# LB_BIT_3IN_3OUT-LARGE-v03_1_1x.net
KiCad netlist of a schematic drawn in EAGLE
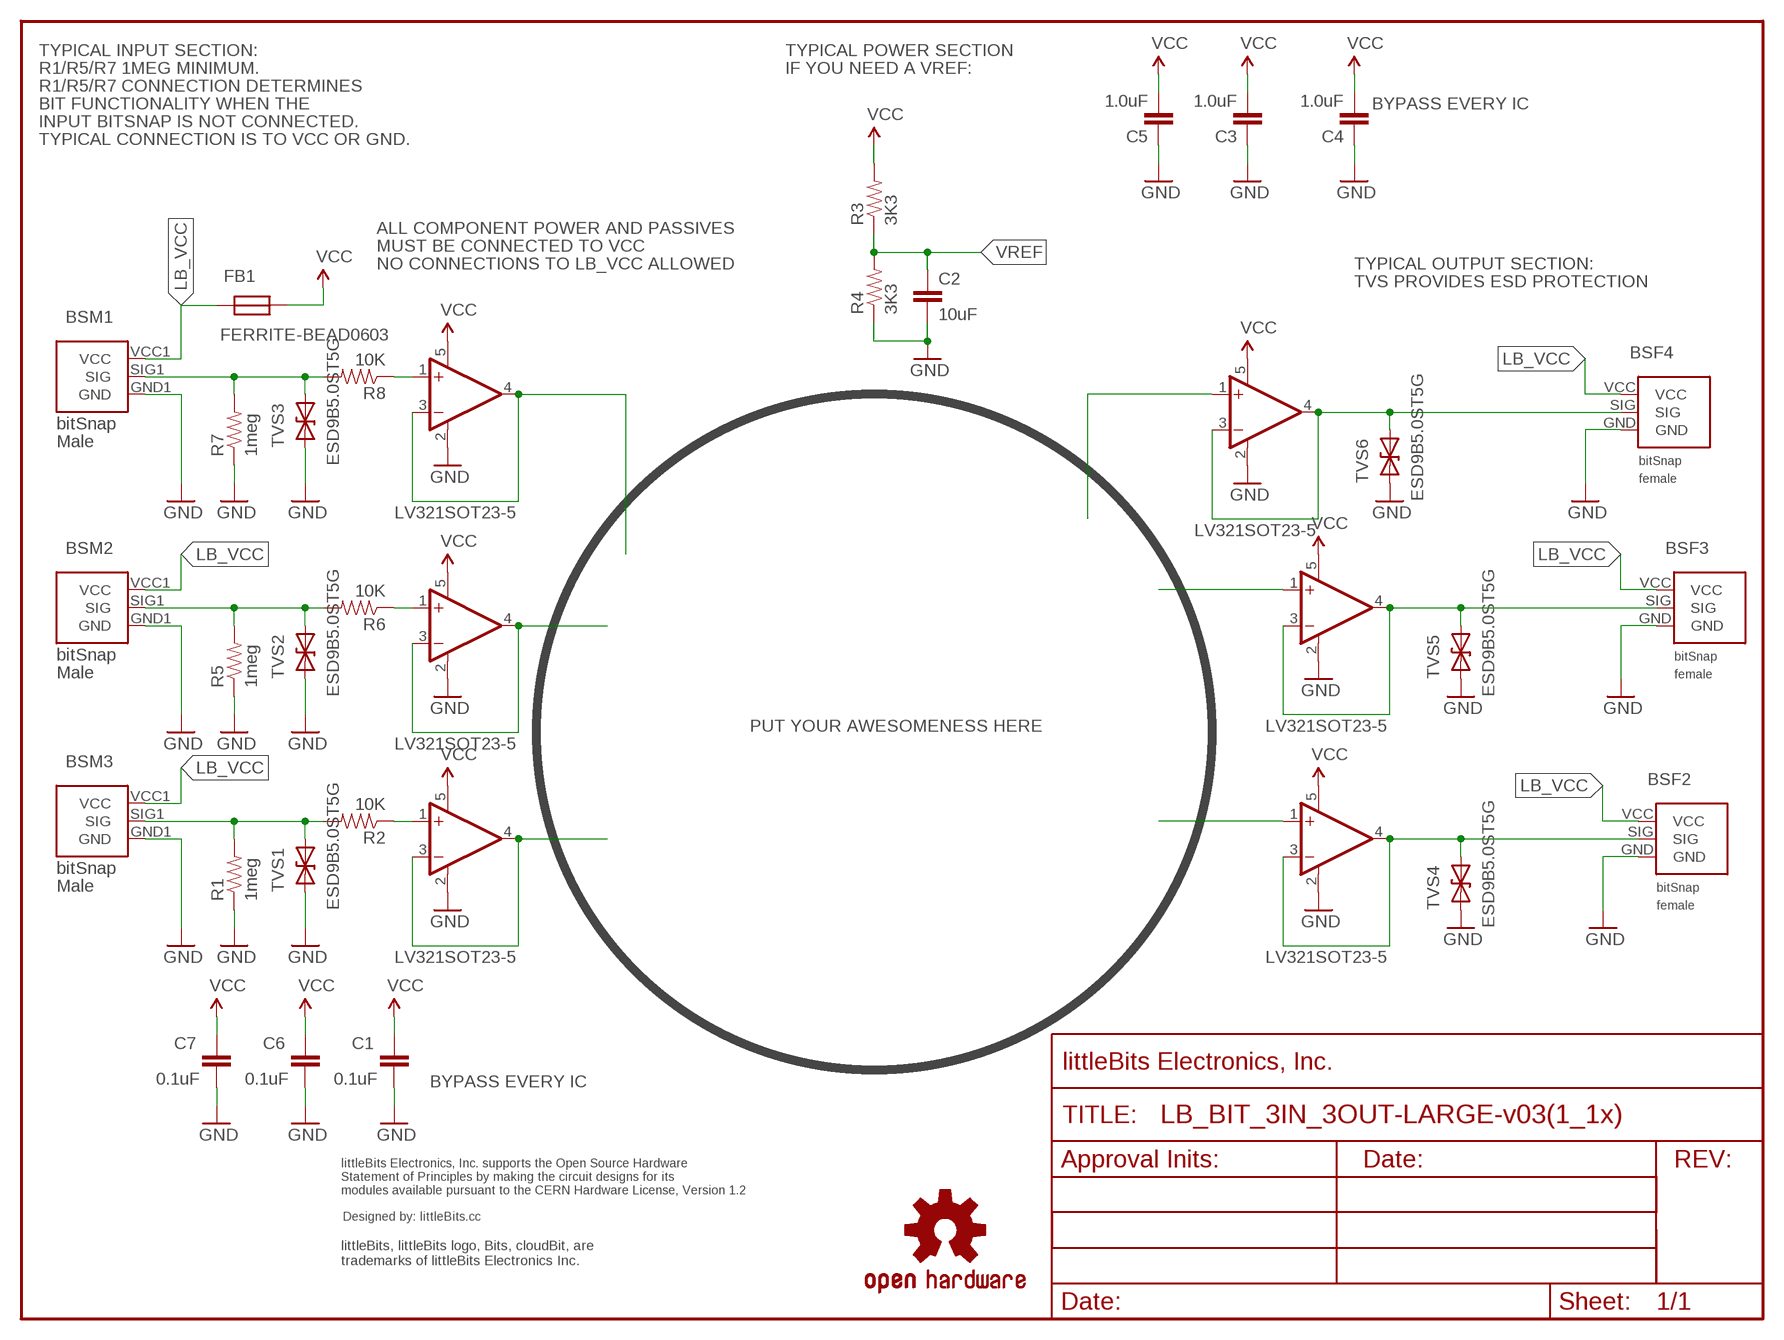
[diagram p0: schematic, sheet 1]

(export (version "E")
  (design (tool "Eeschema 10.0.6"))
  (components
    (comp (ref "BSF2")
      (value "BITSNAP_V03_FEMALE")
      (footprint "eagle-import:BITSNAP_V03_FEMALE")
      (libsource (lib "eagle-import") (part "BITSNAP_V03_FEMALE"))
    )
    (comp (ref "BSF3")
      (value "BITSNAP_V03_FEMALE")
      (footprint "eagle-import:BITSNAP_V03_FEMALE")
      (libsource (lib "eagle-import") (part "BITSNAP_V03_FEMALE"))
    )
    (comp (ref "BSF4")
      (value "BITSNAP_V03_FEMALE")
      (footprint "eagle-import:BITSNAP_V03_FEMALE")
      (libsource (lib "eagle-import") (part "BITSNAP_V03_FEMALE"))
    )
    (comp (ref "BSM1")
      (value "BITSNAP_V03_MALE")
      (footprint "eagle-import:BITSNAP_V03_MALE")
      (libsource (lib "eagle-import") (part "BITSNAP_V03_MALE"))
    )
    (comp (ref "BSM2")
      (value "BITSNAP_V03_MALE")
      (footprint "eagle-import:BITSNAP_V03_MALE")
      (libsource (lib "eagle-import") (part "BITSNAP_V03_MALE"))
    )
    (comp (ref "BSM3")
      (value "BITSNAP_V03_MALE")
      (footprint "eagle-import:BITSNAP_V03_MALE")
      (libsource (lib "eagle-import") (part "BITSNAP_V03_MALE"))
    )
    (comp (ref "C1")
      (value "0.1uF")
      (footprint "eagle-import:CAP-0603")
      (libsource (lib "eagle-import") (part "CAPCAP-0603"))
    )
    (comp (ref "C2")
      (value "10uF")
      (footprint "eagle-import:CAP-0603")
      (libsource (lib "eagle-import") (part "CAPCAP-0603"))
    )
    (comp (ref "C3")
      (value "1.0uF")
      (footprint "eagle-import:CAP-0603")
      (libsource (lib "eagle-import") (part "CAPCAP-0603"))
    )
    (comp (ref "C4")
      (value "1.0uF")
      (footprint "eagle-import:CAP-0603")
      (libsource (lib "eagle-import") (part "CAPCAP-0603"))
    )
    (comp (ref "C5")
      (value "1.0uF")
      (footprint "eagle-import:CAP-0603")
      (libsource (lib "eagle-import") (part "CAPCAP-0603"))
    )
    (comp (ref "C6")
      (value "0.1uF")
      (footprint "eagle-import:CAP-0603")
      (libsource (lib "eagle-import") (part "CAPCAP-0603"))
    )
    (comp (ref "C7")
      (value "0.1uF")
      (footprint "eagle-import:CAP-0603")
      (libsource (lib "eagle-import") (part "CAPCAP-0603"))
    )
    (comp (ref "FB1")
      (value "FERRITE-BEAD0603")
      (footprint "eagle-import:R0603")
      (libsource (lib "eagle-import") (part "FERRITE-BEAD0603"))
    )
    (comp (ref "FRAME1")
      (value "FRAME-LETTER")
      (footprint "eagle-import:FABDWG01-OHW")
      (libsource (lib "eagle-import") (part "FRAME-LETTER"))
    )
    (comp (ref "R1")
      (value "1meg")
      (footprint "eagle-import:RES-0603")
      (libsource (lib "eagle-import") (part "RESISTOR0603"))
    )
    (comp (ref "R2")
      (value "10K")
      (footprint "eagle-import:RES-0603")
      (libsource (lib "eagle-import") (part "RESISTOR0603"))
    )
    (comp (ref "R3")
      (value "3K3")
      (footprint "eagle-import:RES-0603")
      (libsource (lib "eagle-import") (part "RESISTOR0603"))
    )
    (comp (ref "R4")
      (value "3K3")
      (footprint "eagle-import:RES-0603")
      (libsource (lib "eagle-import") (part "RESISTOR0603"))
    )
    (comp (ref "R5")
      (value "1meg")
      (footprint "eagle-import:RES-0603")
      (libsource (lib "eagle-import") (part "RESISTOR0603"))
    )
    (comp (ref "R6")
      (value "10K")
      (footprint "eagle-import:RES-0603")
      (libsource (lib "eagle-import") (part "RESISTOR0603"))
    )
    (comp (ref "R7")
      (value "1meg")
      (footprint "eagle-import:RES-0603")
      (libsource (lib "eagle-import") (part "RESISTOR0603"))
    )
    (comp (ref "R8")
      (value "10K")
      (footprint "eagle-import:RES-0603")
      (libsource (lib "eagle-import") (part "RESISTOR0603"))
    )
    (comp (ref "TVS1")
      (value "ESD9B5.0ST5G")
      (footprint "eagle-import:SOD-923")
      (libsource (lib "eagle-import") (part "DIODE-TVSSOD-923"))
    )
    (comp (ref "TVS2")
      (value "ESD9B5.0ST5G")
      (footprint "eagle-import:SOD-923")
      (libsource (lib "eagle-import") (part "DIODE-TVSSOD-923"))
    )
    (comp (ref "TVS3")
      (value "ESD9B5.0ST5G")
      (footprint "eagle-import:SOD-923")
      (libsource (lib "eagle-import") (part "DIODE-TVSSOD-923"))
    )
    (comp (ref "TVS4")
      (value "ESD9B5.0ST5G")
      (footprint "eagle-import:SOD-923")
      (libsource (lib "eagle-import") (part "DIODE-TVSSOD-923"))
    )
    (comp (ref "TVS5")
      (value "ESD9B5.0ST5G")
      (footprint "eagle-import:SOD-923")
      (libsource (lib "eagle-import") (part "DIODE-TVSSOD-923"))
    )
    (comp (ref "TVS6")
      (value "ESD9B5.0ST5G")
      (footprint "eagle-import:SOD-923")
      (libsource (lib "eagle-import") (part "DIODE-TVSSOD-923"))
    )
    (comp (ref "U$1")
      (value "OSHWCREDIT")
      (footprint "eagle-import:OSHWCREDIT")
      (libsource (lib "eagle-import") (part "OSHWCREDIT"))
    )
    (comp (ref "U$70")
      (value "OSHW-LOGOL")
      (footprint "eagle-import:OSHW-LOGO-L")
      (libsource (lib "eagle-import") (part "OSHW-LOGOL"))
    )
    (comp (ref "U1")
      (value "LV321SOT23-5")
      (footprint "eagle-import:SOT23-5")
      (libsource (lib "eagle-import") (part "LV321SOT23-5"))
    )
    (comp (ref "U2")
      (value "LV321SOT23-5")
      (footprint "eagle-import:SOT23-5")
      (libsource (lib "eagle-import") (part "LV321SOT23-5"))
    )
    (comp (ref "U3")
      (value "LV321SOT23-5")
      (footprint "eagle-import:SOT23-5")
      (libsource (lib "eagle-import") (part "LV321SOT23-5"))
    )
    (comp (ref "U4")
      (value "LV321SOT23-5")
      (footprint "eagle-import:SOT23-5")
      (libsource (lib "eagle-import") (part "LV321SOT23-5"))
    )
    (comp (ref "U5")
      (value "LV321SOT23-5")
      (footprint "eagle-import:SOT23-5")
      (libsource (lib "eagle-import") (part "LV321SOT23-5"))
    )
    (comp (ref "U6")
      (value "LV321SOT23-5")
      (footprint "eagle-import:SOT23-5")
      (libsource (lib "eagle-import") (part "LV321SOT23-5"))
    )
  )
  (nets
    (net (code "1") (name "GND") (class "Default")
      (node (ref "BSF2") (pin "GND") (pinfunction "GND_GND") (pintype "bidirectional"))
      (node (ref "BSF3") (pin "GND") (pinfunction "GND_GND") (pintype "bidirectional"))
      (node (ref "BSF4") (pin "GND") (pinfunction "GND_GND") (pintype "bidirectional"))
      (node (ref "BSM1") (pin "GND1") (pinfunction "GND_GND1") (pintype "bidirectional"))
      (node (ref "BSM2") (pin "GND1") (pinfunction "GND_GND1") (pintype "bidirectional"))
      (node (ref "BSM3") (pin "GND1") (pinfunction "GND_GND1") (pintype "bidirectional"))
      (node (ref "C1") (pin "2") (pinfunction "2_2") (pintype "passive"))
      (node (ref "C2") (pin "2") (pinfunction "2_2") (pintype "passive"))
      (node (ref "C3") (pin "1") (pinfunction "1_1") (pintype "passive"))
      (node (ref "C4") (pin "1") (pinfunction "1_1") (pintype "passive"))
      (node (ref "C5") (pin "1") (pinfunction "1_1") (pintype "passive"))
      (node (ref "C6") (pin "2") (pinfunction "2_2") (pintype "passive"))
      (node (ref "C7") (pin "2") (pinfunction "2_2") (pintype "passive"))
      (node (ref "R1") (pin "1") (pinfunction "1_1") (pintype "passive"))
      (node (ref "R4") (pin "1") (pinfunction "1_1") (pintype "passive"))
      (node (ref "R5") (pin "1") (pinfunction "1_1") (pintype "passive"))
      (node (ref "R7") (pin "1") (pinfunction "1_1") (pintype "passive"))
      (node (ref "TVS1") (pin "1") (pinfunction "A_1") (pintype "passive"))
      (node (ref "TVS2") (pin "1") (pinfunction "A_1") (pintype "passive"))
      (node (ref "TVS3") (pin "1") (pinfunction "A_1") (pintype "passive"))
      (node (ref "TVS4") (pin "1") (pinfunction "A_1") (pintype "passive"))
      (node (ref "TVS5") (pin "1") (pinfunction "A_1") (pintype "passive"))
      (node (ref "TVS6") (pin "1") (pinfunction "A_1") (pintype "passive"))
      (node (ref "U1") (pin "2") (pinfunction "V-_2") (pintype "power_in"))
      (node (ref "U2") (pin "2") (pinfunction "V-_2") (pintype "power_in"))
      (node (ref "U3") (pin "2") (pinfunction "V-_2") (pintype "power_in"))
      (node (ref "U4") (pin "2") (pinfunction "V-_2") (pintype "power_in"))
      (node (ref "U5") (pin "2") (pinfunction "V-_2") (pintype "power_in"))
      (node (ref "U6") (pin "2") (pinfunction "V-_2") (pintype "power_in"))
    )
    (net (code "2") (name "LB_VCC") (class "Default")
      (node (ref "BSF2") (pin "VCC") (pinfunction "VCC_VCC") (pintype "bidirectional"))
      (node (ref "BSF3") (pin "VCC") (pinfunction "VCC_VCC") (pintype "bidirectional"))
      (node (ref "BSF4") (pin "VCC") (pinfunction "VCC_VCC") (pintype "bidirectional"))
      (node (ref "BSM1") (pin "VCC1") (pinfunction "VCC_VCC1") (pintype "bidirectional"))
      (node (ref "BSM2") (pin "VCC1") (pinfunction "VCC_VCC1") (pintype "bidirectional"))
      (node (ref "BSM3") (pin "VCC1") (pinfunction "VCC_VCC1") (pintype "bidirectional"))
      (node (ref "FB1") (pin "2") (pinfunction "P$2_2") (pintype "bidirectional"))
    )
    (net (code "3") (name "Net-(BSM1-SIG)") (class "Default")
      (node (ref "BSM1") (pin "SIG1") (pinfunction "SIG_SIG1") (pintype "bidirectional"))
      (node (ref "R7") (pin "2") (pinfunction "2_2") (pintype "passive"))
      (node (ref "R8") (pin "2") (pinfunction "2_2") (pintype "passive"))
      (node (ref "TVS3") (pin "2") (pinfunction "C_2") (pintype "passive"))
    )
    (net (code "4") (name "Net-(BSM2-SIG)") (class "Default")
      (node (ref "BSM2") (pin "SIG1") (pinfunction "SIG_SIG1") (pintype "bidirectional"))
      (node (ref "R5") (pin "2") (pinfunction "2_2") (pintype "passive"))
      (node (ref "R6") (pin "2") (pinfunction "2_2") (pintype "passive"))
      (node (ref "TVS2") (pin "2") (pinfunction "C_2") (pintype "passive"))
    )
    (net (code "5") (name "Net-(BSM3-SIG)") (class "Default")
      (node (ref "BSM3") (pin "SIG1") (pinfunction "SIG_SIG1") (pintype "bidirectional"))
      (node (ref "R1") (pin "2") (pinfunction "2_2") (pintype "passive"))
      (node (ref "R2") (pin "2") (pinfunction "2_2") (pintype "passive"))
      (node (ref "TVS1") (pin "2") (pinfunction "C_2") (pintype "passive"))
    )
    (net (code "6") (name "Net-(TVS4-C)") (class "Default")
      (node (ref "BSF2") (pin "SIG") (pinfunction "SIG_SIG") (pintype "bidirectional"))
      (node (ref "TVS4") (pin "2") (pinfunction "C_2") (pintype "passive"))
      (node (ref "U4") (pin "3") (pinfunction "-IN_3") (pintype "input"))
      (node (ref "U4") (pin "4") (pinfunction "OUT_4") (pintype "output"))
    )
    (net (code "7") (name "Net-(TVS5-C)") (class "Default")
      (node (ref "BSF3") (pin "SIG") (pinfunction "SIG_SIG") (pintype "bidirectional"))
      (node (ref "TVS5") (pin "2") (pinfunction "C_2") (pintype "passive"))
      (node (ref "U5") (pin "3") (pinfunction "-IN_3") (pintype "input"))
      (node (ref "U5") (pin "4") (pinfunction "OUT_4") (pintype "output"))
    )
    (net (code "8") (name "Net-(TVS6-C)") (class "Default")
      (node (ref "BSF4") (pin "SIG") (pinfunction "SIG_SIG") (pintype "bidirectional"))
      (node (ref "TVS6") (pin "2") (pinfunction "C_2") (pintype "passive"))
      (node (ref "U6") (pin "3") (pinfunction "-IN_3") (pintype "input"))
      (node (ref "U6") (pin "4") (pinfunction "OUT_4") (pintype "output"))
    )
    (net (code "9") (name "Net-(U1-+IN)") (class "Default")
      (node (ref "R2") (pin "1") (pinfunction "1_1") (pintype "passive"))
      (node (ref "U1") (pin "1") (pinfunction "+IN_1") (pintype "input"))
    )
    (net (code "10") (name "Net-(U1--IN)") (class "Default")
      (node (ref "U1") (pin "3") (pinfunction "-IN_3") (pintype "input"))
      (node (ref "U1") (pin "4") (pinfunction "OUT_4") (pintype "output"))
    )
    (net (code "11") (name "Net-(U2-+IN)") (class "Default")
      (node (ref "R6") (pin "1") (pinfunction "1_1") (pintype "passive"))
      (node (ref "U2") (pin "1") (pinfunction "+IN_1") (pintype "input"))
    )
    (net (code "12") (name "Net-(U2--IN)") (class "Default")
      (node (ref "U2") (pin "3") (pinfunction "-IN_3") (pintype "input"))
      (node (ref "U2") (pin "4") (pinfunction "OUT_4") (pintype "output"))
    )
    (net (code "13") (name "Net-(U3-+IN)") (class "Default")
      (node (ref "R8") (pin "1") (pinfunction "1_1") (pintype "passive"))
      (node (ref "U3") (pin "1") (pinfunction "+IN_1") (pintype "input"))
    )
    (net (code "14") (name "Net-(U3--IN)") (class "Default")
      (node (ref "U3") (pin "3") (pinfunction "-IN_3") (pintype "input"))
      (node (ref "U3") (pin "4") (pinfunction "OUT_4") (pintype "output"))
    )
    (net (code "15") (name "VCC") (class "Default")
      (node (ref "C1") (pin "1") (pinfunction "1_1") (pintype "passive"))
      (node (ref "C3") (pin "2") (pinfunction "2_2") (pintype "passive"))
      (node (ref "C4") (pin "2") (pinfunction "2_2") (pintype "passive"))
      (node (ref "C5") (pin "2") (pinfunction "2_2") (pintype "passive"))
      (node (ref "C6") (pin "1") (pinfunction "1_1") (pintype "passive"))
      (node (ref "C7") (pin "1") (pinfunction "1_1") (pintype "passive"))
      (node (ref "FB1") (pin "1") (pinfunction "P$1_1") (pintype "bidirectional"))
      (node (ref "R3") (pin "2") (pinfunction "2_2") (pintype "passive"))
      (node (ref "U1") (pin "5") (pinfunction "V+_5") (pintype "power_in"))
      (node (ref "U2") (pin "5") (pinfunction "V+_5") (pintype "power_in"))
      (node (ref "U3") (pin "5") (pinfunction "V+_5") (pintype "power_in"))
      (node (ref "U4") (pin "5") (pinfunction "V+_5") (pintype "power_in"))
      (node (ref "U5") (pin "5") (pinfunction "V+_5") (pintype "power_in"))
      (node (ref "U6") (pin "5") (pinfunction "V+_5") (pintype "power_in"))
    )
    (net (code "16") (name "VREF") (class "Default")
      (node (ref "C2") (pin "1") (pinfunction "1_1") (pintype "passive"))
      (node (ref "R3") (pin "1") (pinfunction "1_1") (pintype "passive"))
      (node (ref "R4") (pin "2") (pinfunction "2_2") (pintype "passive"))
    )
    (net (code "17") (name "unconnected-(U4-+IN-Pad1)") (class "Default")
      (node (ref "U4") (pin "1") (pinfunction "+IN_1") (pintype "input"))
    )
    (net (code "18") (name "unconnected-(U5-+IN-Pad1)") (class "Default")
      (node (ref "U5") (pin "1") (pinfunction "+IN_1") (pintype "input"))
    )
    (net (code "19") (name "unconnected-(U6-+IN-Pad1)") (class "Default")
      (node (ref "U6") (pin "1") (pinfunction "+IN_1") (pintype "input"))
    )
  )
)
